# DMXto16Ch.net
KiCad netlist of a schematic drawn in EAGLE
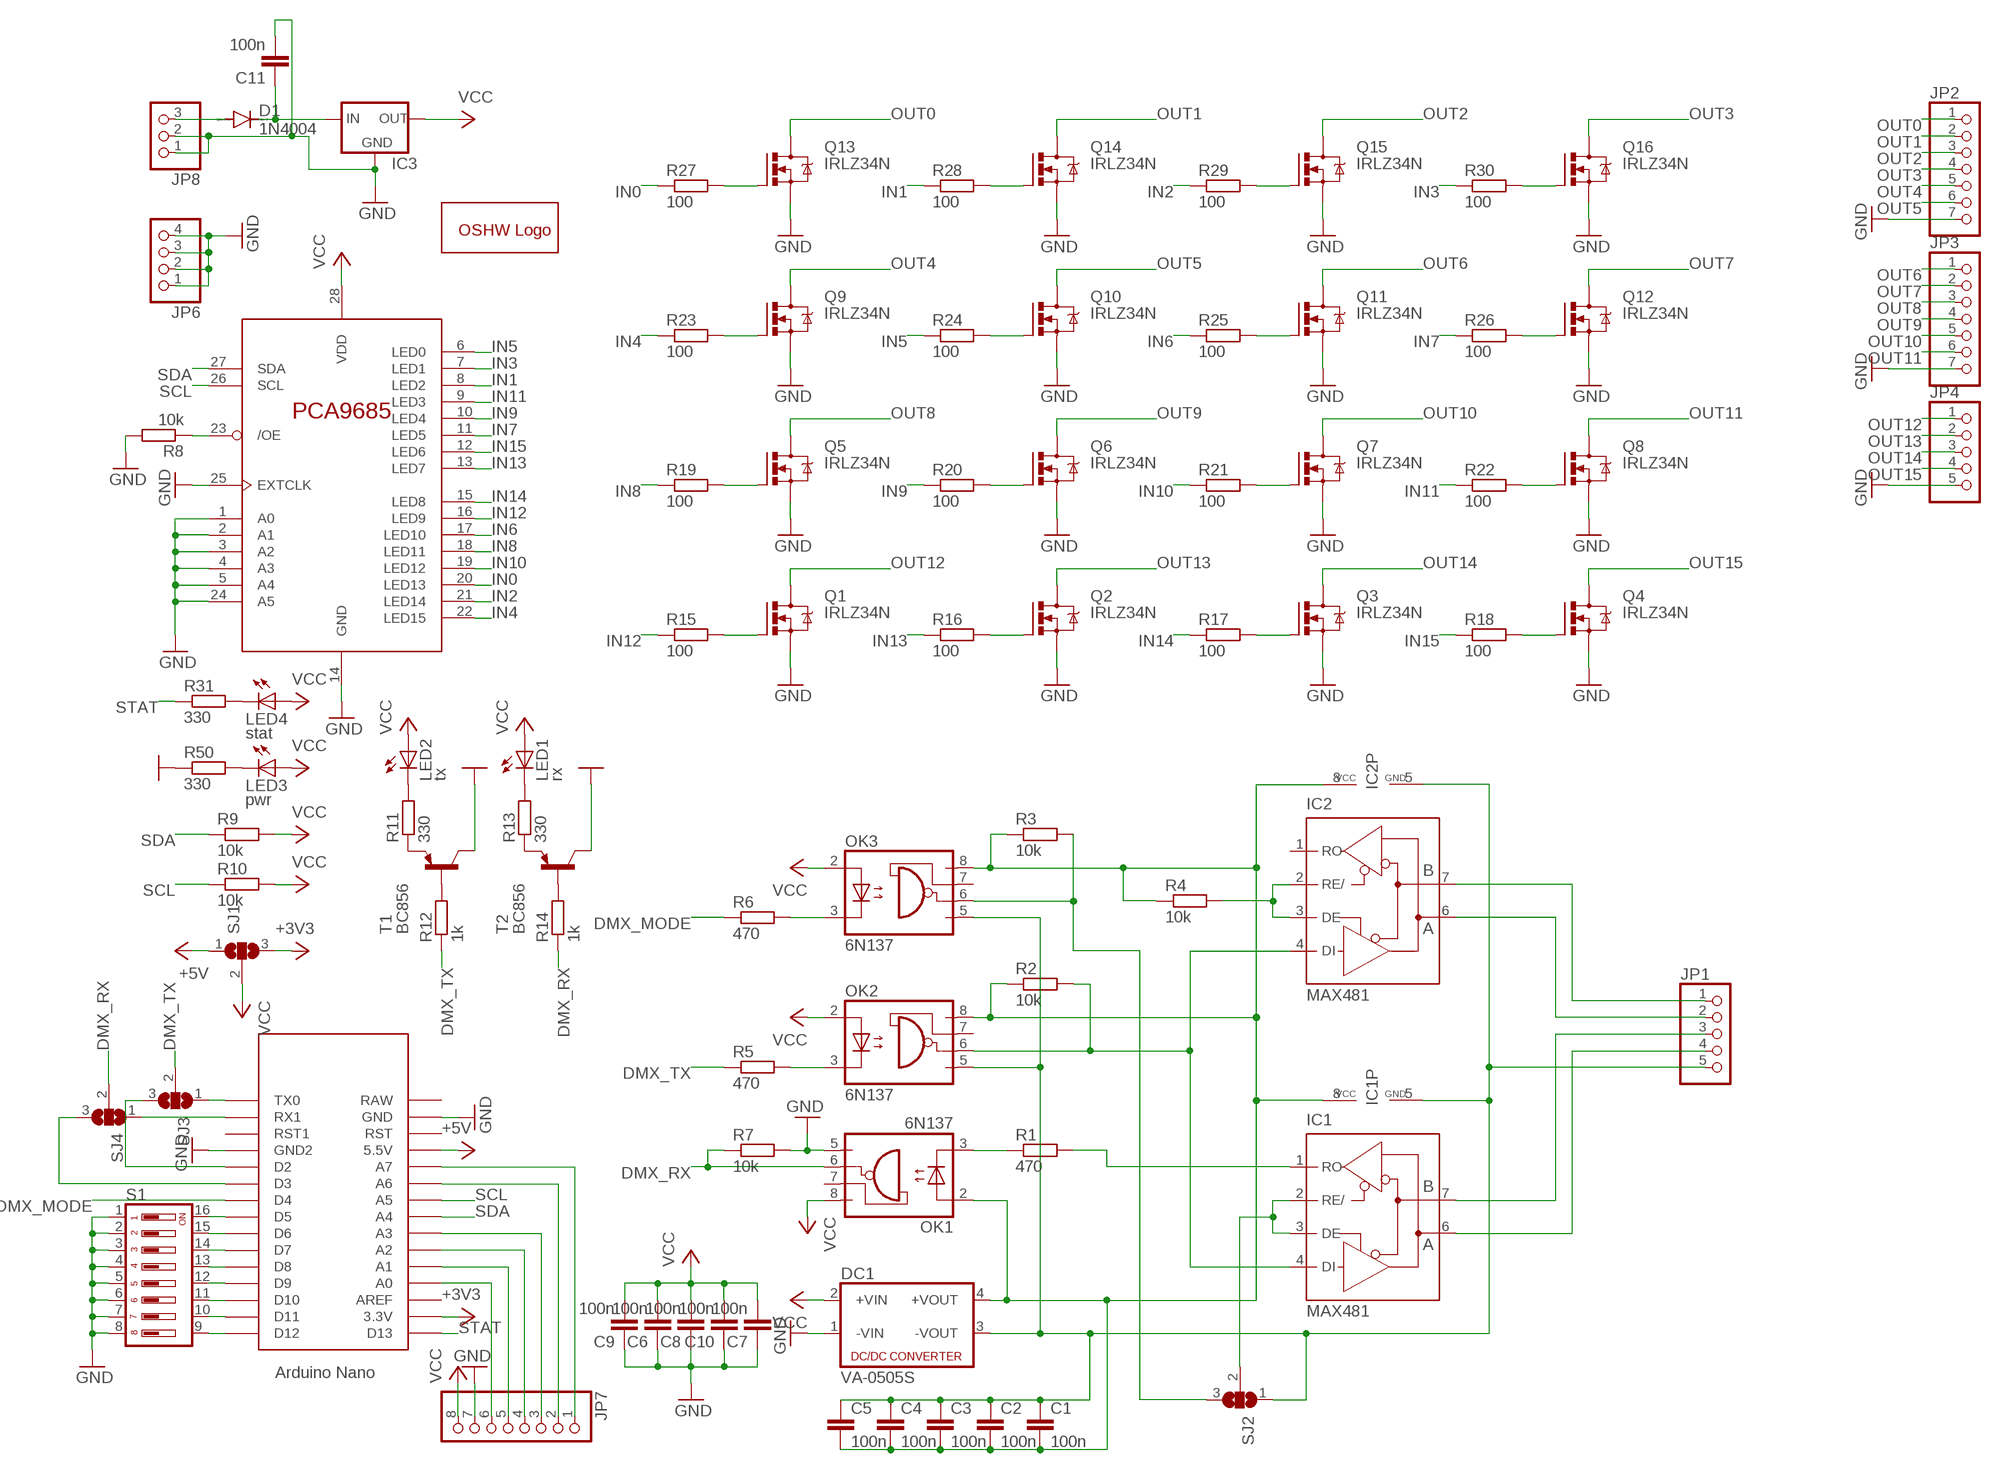
[diagram p0: schematic, sheet 1]

(export (version "E")
  (design (tool "Eeschema 10.0.6"))
  (components
    (comp (ref "C1")
      (value "100n")
      (footprint "eagle-import:C1206")
      (libsource (lib "eagle-import") (part "C-EUC1206"))
    )
    (comp (ref "C2")
      (value "100n")
      (footprint "eagle-import:C1206")
      (libsource (lib "eagle-import") (part "C-EUC1206"))
    )
    (comp (ref "C3")
      (value "100n")
      (footprint "eagle-import:C1206")
      (libsource (lib "eagle-import") (part "C-EUC1206"))
    )
    (comp (ref "C4")
      (value "100n")
      (footprint "eagle-import:C1206")
      (libsource (lib "eagle-import") (part "C-EUC1206"))
    )
    (comp (ref "C5")
      (value "100n")
      (footprint "eagle-import:C1206")
      (libsource (lib "eagle-import") (part "C-EUC1206"))
    )
    (comp (ref "C6")
      (value "100n")
      (footprint "eagle-import:C1206")
      (libsource (lib "eagle-import") (part "C-EUC1206"))
    )
    (comp (ref "C7")
      (value "100n")
      (footprint "eagle-import:C1206")
      (libsource (lib "eagle-import") (part "C-EUC1206"))
    )
    (comp (ref "C8")
      (value "100n")
      (footprint "eagle-import:C1206")
      (libsource (lib "eagle-import") (part "C-EUC1206"))
    )
    (comp (ref "C9")
      (value "100n")
      (footprint "eagle-import:C1206")
      (libsource (lib "eagle-import") (part "C-EUC1206"))
    )
    (comp (ref "C10")
      (value "100n")
      (footprint "eagle-import:C1206")
      (libsource (lib "eagle-import") (part "C-EUC1206"))
    )
    (comp (ref "C11")
      (value "100n")
      (footprint "eagle-import:C1206")
      (libsource (lib "eagle-import") (part "C-EUC1206"))
    )
    (comp (ref "D1")
      (value "1N4004")
      (footprint "eagle-import:DO41-10")
      (libsource (lib "eagle-import") (part "1N4004"))
    )
    (comp (ref "DC1")
      (value "VA-0505S")
      (footprint "eagle-import:4SIL")
      (libsource (lib "eagle-import") (part "VA-?S0505"))
    )
    (comp (ref "GOLD_ORB_SM1")
      (value "OSHWLOGOLOGO5MM")
      (footprint "eagle-import:OSHW_5MM")
      (libsource (lib "eagle-import") (part "OSHWLOGOLOGO5MM"))
    )
    (comp (ref "IC1")
      (value "MAX481")
      (footprint "eagle-import:DIL08")
      (libsource (lib "eagle-import") (part "MAX481CPA"))
    )
    (comp (ref "IC2")
      (value "MAX481")
      (footprint "eagle-import:DIL08")
      (libsource (lib "eagle-import") (part "MAX481CPA"))
    )
    (comp (ref "IC3")
      (value "78XXS")
      (footprint "eagle-import:78XXS")
      (libsource (lib "eagle-import") (part "78XXS"))
    )
    (comp (ref "JP1")
      (value "PINHD-1X5")
      (footprint "eagle-import:1X05")
      (libsource (lib "eagle-import") (part "PINHD-1X5"))
    )
    (comp (ref "JP2")
      (value "PINHD-1X7")
      (footprint "eagle-import:1X07")
      (libsource (lib "eagle-import") (part "PINHD-1X7"))
    )
    (comp (ref "JP3")
      (value "PINHD-1X7")
      (footprint "eagle-import:1X07")
      (libsource (lib "eagle-import") (part "PINHD-1X7"))
    )
    (comp (ref "JP4")
      (value "PINHD-1X5")
      (footprint "eagle-import:1X05")
      (libsource (lib "eagle-import") (part "PINHD-1X5"))
    )
    (comp (ref "JP6")
      (value "PINHD-1X4")
      (footprint "eagle-import:1X04")
      (libsource (lib "eagle-import") (part "PINHD-1X4"))
    )
    (comp (ref "JP7")
      (value "PINHD-1X8")
      (footprint "eagle-import:1X08")
      (libsource (lib "eagle-import") (part "PINHD-1X8"))
    )
    (comp (ref "JP8")
      (value "PINHD-1X3")
      (footprint "eagle-import:1X03")
      (libsource (lib "eagle-import") (part "PINHD-1X3"))
    )
    (comp (ref "LED1")
      (value "rx")
      (footprint "eagle-import:1206")
      (libsource (lib "eagle-import") (part "LEDSMT1206"))
    )
    (comp (ref "LED2")
      (value "tx")
      (footprint "eagle-import:1206")
      (libsource (lib "eagle-import") (part "LEDSMT1206"))
    )
    (comp (ref "LED3")
      (value "pwr")
      (footprint "eagle-import:1206")
      (libsource (lib "eagle-import") (part "LEDSMT1206"))
    )
    (comp (ref "LED4")
      (value "stat")
      (footprint "eagle-import:1206")
      (libsource (lib "eagle-import") (part "LEDSMT1206"))
    )
    (comp (ref "OK1")
      (value "6N137")
      (footprint "eagle-import:DIL08")
      (libsource (lib "eagle-import") (part "6N137"))
    )
    (comp (ref "OK2")
      (value "6N137")
      (footprint "eagle-import:DIL08")
      (libsource (lib "eagle-import") (part "6N137"))
    )
    (comp (ref "OK3")
      (value "6N137")
      (footprint "eagle-import:DIL08")
      (libsource (lib "eagle-import") (part "6N137"))
    )
    (comp (ref "Q1")
      (value "IRLZ34N")
      (footprint "eagle-import:TO220BV")
      (libsource (lib "eagle-import") (part "IRF520"))
    )
    (comp (ref "Q2")
      (value "IRLZ34N")
      (footprint "eagle-import:TO220BV")
      (libsource (lib "eagle-import") (part "IRF520"))
    )
    (comp (ref "Q3")
      (value "IRLZ34N")
      (footprint "eagle-import:TO220BV")
      (libsource (lib "eagle-import") (part "IRF520"))
    )
    (comp (ref "Q4")
      (value "IRLZ34N")
      (footprint "eagle-import:TO220BV")
      (libsource (lib "eagle-import") (part "IRF520"))
    )
    (comp (ref "Q5")
      (value "IRLZ34N")
      (footprint "eagle-import:TO220BV")
      (libsource (lib "eagle-import") (part "IRF520"))
    )
    (comp (ref "Q6")
      (value "IRLZ34N")
      (footprint "eagle-import:TO220BV")
      (libsource (lib "eagle-import") (part "IRF520"))
    )
    (comp (ref "Q7")
      (value "IRLZ34N")
      (footprint "eagle-import:TO220BV")
      (libsource (lib "eagle-import") (part "IRF520"))
    )
    (comp (ref "Q8")
      (value "IRLZ34N")
      (footprint "eagle-import:TO220BV")
      (libsource (lib "eagle-import") (part "IRF520"))
    )
    (comp (ref "Q9")
      (value "IRLZ34N")
      (footprint "eagle-import:TO220BV")
      (libsource (lib "eagle-import") (part "IRF520"))
    )
    (comp (ref "Q10")
      (value "IRLZ34N")
      (footprint "eagle-import:TO220BV")
      (libsource (lib "eagle-import") (part "IRF520"))
    )
    (comp (ref "Q11")
      (value "IRLZ34N")
      (footprint "eagle-import:TO220BV")
      (libsource (lib "eagle-import") (part "IRF520"))
    )
    (comp (ref "Q12")
      (value "IRLZ34N")
      (footprint "eagle-import:TO220BV")
      (libsource (lib "eagle-import") (part "IRF520"))
    )
    (comp (ref "Q13")
      (value "IRLZ34N")
      (footprint "eagle-import:TO220BV")
      (libsource (lib "eagle-import") (part "IRF520"))
    )
    (comp (ref "Q14")
      (value "IRLZ34N")
      (footprint "eagle-import:TO220BV")
      (libsource (lib "eagle-import") (part "IRF520"))
    )
    (comp (ref "Q15")
      (value "IRLZ34N")
      (footprint "eagle-import:TO220BV")
      (libsource (lib "eagle-import") (part "IRF520"))
    )
    (comp (ref "Q16")
      (value "IRLZ34N")
      (footprint "eagle-import:TO220BV")
      (libsource (lib "eagle-import") (part "IRF520"))
    )
    (comp (ref "R1")
      (value "470")
      (footprint "eagle-import:R1206")
      (libsource (lib "eagle-import") (part "R-EU_R1206"))
    )
    (comp (ref "R2")
      (value "10k")
      (footprint "eagle-import:R1206")
      (libsource (lib "eagle-import") (part "R-EU_R1206"))
    )
    (comp (ref "R3")
      (value "10k")
      (footprint "eagle-import:R1206")
      (libsource (lib "eagle-import") (part "R-EU_R1206"))
    )
    (comp (ref "R4")
      (value "10k")
      (footprint "eagle-import:R1206")
      (libsource (lib "eagle-import") (part "R-EU_R1206"))
    )
    (comp (ref "R5")
      (value "470")
      (footprint "eagle-import:R1206")
      (libsource (lib "eagle-import") (part "R-EU_R1206"))
    )
    (comp (ref "R6")
      (value "470")
      (footprint "eagle-import:R1206")
      (libsource (lib "eagle-import") (part "R-EU_R1206"))
    )
    (comp (ref "R7")
      (value "10k")
      (footprint "eagle-import:R1206")
      (libsource (lib "eagle-import") (part "R-EU_R1206"))
    )
    (comp (ref "R8")
      (value "10k")
      (footprint "eagle-import:R1206")
      (libsource (lib "eagle-import") (part "R-EU_R1206"))
    )
    (comp (ref "R9")
      (value "10k")
      (footprint "eagle-import:R1206")
      (libsource (lib "eagle-import") (part "R-EU_R1206"))
    )
    (comp (ref "R10")
      (value "10k")
      (footprint "eagle-import:R1206")
      (libsource (lib "eagle-import") (part "R-EU_R1206"))
    )
    (comp (ref "R11")
      (value "330")
      (footprint "eagle-import:R1206")
      (libsource (lib "eagle-import") (part "R-EU_R1206"))
    )
    (comp (ref "R12")
      (value "1k")
      (footprint "eagle-import:R1206")
      (libsource (lib "eagle-import") (part "R-EU_R1206"))
    )
    (comp (ref "R13")
      (value "330")
      (footprint "eagle-import:R1206")
      (libsource (lib "eagle-import") (part "R-EU_R1206"))
    )
    (comp (ref "R14")
      (value "1k")
      (footprint "eagle-import:R1206")
      (libsource (lib "eagle-import") (part "R-EU_R1206"))
    )
    (comp (ref "R15")
      (value "100")
      (footprint "eagle-import:R1206")
      (libsource (lib "eagle-import") (part "R-EU_R1206"))
    )
    (comp (ref "R16")
      (value "100")
      (footprint "eagle-import:R1206")
      (libsource (lib "eagle-import") (part "R-EU_R1206"))
    )
    (comp (ref "R17")
      (value "100")
      (footprint "eagle-import:R1206")
      (libsource (lib "eagle-import") (part "R-EU_R1206"))
    )
    (comp (ref "R18")
      (value "100")
      (footprint "eagle-import:R1206")
      (libsource (lib "eagle-import") (part "R-EU_R1206"))
    )
    (comp (ref "R19")
      (value "100")
      (footprint "eagle-import:R1206")
      (libsource (lib "eagle-import") (part "R-EU_R1206"))
    )
    (comp (ref "R20")
      (value "100")
      (footprint "eagle-import:R1206")
      (libsource (lib "eagle-import") (part "R-EU_R1206"))
    )
    (comp (ref "R21")
      (value "100")
      (footprint "eagle-import:R1206")
      (libsource (lib "eagle-import") (part "R-EU_R1206"))
    )
    (comp (ref "R22")
      (value "100")
      (footprint "eagle-import:R1206")
      (libsource (lib "eagle-import") (part "R-EU_R1206"))
    )
    (comp (ref "R23")
      (value "100")
      (footprint "eagle-import:R1206")
      (libsource (lib "eagle-import") (part "R-EU_R1206"))
    )
    (comp (ref "R24")
      (value "100")
      (footprint "eagle-import:R1206")
      (libsource (lib "eagle-import") (part "R-EU_R1206"))
    )
    (comp (ref "R25")
      (value "100")
      (footprint "eagle-import:R1206")
      (libsource (lib "eagle-import") (part "R-EU_R1206"))
    )
    (comp (ref "R26")
      (value "100")
      (footprint "eagle-import:R1206")
      (libsource (lib "eagle-import") (part "R-EU_R1206"))
    )
    (comp (ref "R27")
      (value "100")
      (footprint "eagle-import:R1206")
      (libsource (lib "eagle-import") (part "R-EU_R1206"))
    )
    (comp (ref "R28")
      (value "100")
      (footprint "eagle-import:R1206")
      (libsource (lib "eagle-import") (part "R-EU_R1206"))
    )
    (comp (ref "R29")
      (value "100")
      (footprint "eagle-import:R1206")
      (libsource (lib "eagle-import") (part "R-EU_R1206"))
    )
    (comp (ref "R30")
      (value "100")
      (footprint "eagle-import:R1206")
      (libsource (lib "eagle-import") (part "R-EU_R1206"))
    )
    (comp (ref "R31")
      (value "330")
      (footprint "eagle-import:R1206")
      (libsource (lib "eagle-import") (part "R-EU_R1206"))
    )
    (comp (ref "R50")
      (value "330")
      (footprint "eagle-import:R1206")
      (libsource (lib "eagle-import") (part "R-EU_R1206"))
    )
    (comp (ref "S1")
      (value "DIP08YL")
      (footprint "eagle-import:DIP08YL")
      (libsource (lib "eagle-import") (part "DIP08YL"))
    )
    (comp (ref "SJ1")
      (value "SJ2W")
      (footprint "eagle-import:SJ_2")
      (libsource (lib "eagle-import") (part "SJ2W"))
    )
    (comp (ref "SJ2")
      (value "SJ2W")
      (footprint "eagle-import:SJ_2")
      (libsource (lib "eagle-import") (part "SJ2W"))
    )
    (comp (ref "SJ3")
      (value "SJ2W")
      (footprint "eagle-import:SJ_2")
      (libsource (lib "eagle-import") (part "SJ2W"))
    )
    (comp (ref "SJ4")
      (value "SJ2W")
      (footprint "eagle-import:SJ_2")
      (libsource (lib "eagle-import") (part "SJ2W"))
    )
    (comp (ref "T1")
      (value "BC856")
      (footprint "eagle-import:SOT23-BCE")
      (libsource (lib "eagle-import") (part "-PNP-SOT23-BCE"))
    )
    (comp (ref "T2")
      (value "BC856")
      (footprint "eagle-import:SOT23-BCE")
      (libsource (lib "eagle-import") (part "-PNP-SOT23-BCE"))
    )
    (comp (ref "U$1")
      (value "NANO")
      (footprint "eagle-import:NANO")
      (libsource (lib "eagle-import") (part "NANO"))
    )
    (comp (ref "U$2")
      (value "PCA9685PW")
      (footprint "eagle-import:TSSOP28")
      (libsource (lib "eagle-import") (part "PCA9685PW"))
    )
  )
  (nets
    (net (code "1") (name "+3V3") (class "Default")
      (node (ref "SJ1") (pin "3") (pinfunction "3_3") (pintype "passive"))
      (node (ref "U$1") (pin "3.3V") (pinfunction "3.3V_3.3V") (pintype "bidirectional"))
    )
    (net (code "2") (name "+5V") (class "Default")
      (node (ref "SJ1") (pin "1") (pinfunction "1_1") (pintype "passive"))
      (node (ref "U$1") (pin "5V") (pinfunction "5.5V_5V") (pintype "bidirectional"))
    )
    (net (code "3") (name "/DMX_MODE") (class "Default")
      (node (ref "R6") (pin "1") (pinfunction "1_1") (pintype "passive"))
      (node (ref "U$1") (pin "D4") (pinfunction "D4_D4") (pintype "bidirectional"))
    )
    (net (code "4") (name "/DMX_RX") (class "Default")
      (node (ref "OK1") (pin "6") (pinfunction "VO_6") (pintype "passive"))
      (node (ref "R14") (pin "1") (pinfunction "1_1") (pintype "passive"))
      (node (ref "R7") (pin "1") (pinfunction "1_1") (pintype "passive"))
      (node (ref "SJ4") (pin "2") (pinfunction "2_2") (pintype "passive"))
    )
    (net (code "5") (name "/DMX_TX") (class "Default")
      (node (ref "R12") (pin "1") (pinfunction "1_1") (pintype "passive"))
      (node (ref "R5") (pin "1") (pinfunction "1_1") (pintype "passive"))
      (node (ref "SJ3") (pin "2") (pinfunction "2_2") (pintype "passive"))
    )
    (net (code "6") (name "/IN0") (class "Default")
      (node (ref "R27") (pin "1") (pinfunction "1_1") (pintype "passive"))
      (node (ref "U$2") (pin "20") (pinfunction "LED13_20") (pintype "bidirectional"))
    )
    (net (code "7") (name "/IN1") (class "Default")
      (node (ref "R28") (pin "1") (pinfunction "1_1") (pintype "passive"))
      (node (ref "U$2") (pin "8") (pinfunction "LED2_8") (pintype "bidirectional"))
    )
    (net (code "8") (name "/IN2") (class "Default")
      (node (ref "R29") (pin "1") (pinfunction "1_1") (pintype "passive"))
      (node (ref "U$2") (pin "21") (pinfunction "LED14_21") (pintype "bidirectional"))
    )
    (net (code "9") (name "/IN3") (class "Default")
      (node (ref "R30") (pin "1") (pinfunction "1_1") (pintype "passive"))
      (node (ref "U$2") (pin "7") (pinfunction "LED1_7") (pintype "bidirectional"))
    )
    (net (code "10") (name "/IN4") (class "Default")
      (node (ref "R23") (pin "1") (pinfunction "1_1") (pintype "passive"))
      (node (ref "U$2") (pin "22") (pinfunction "LED15_22") (pintype "bidirectional"))
    )
    (net (code "11") (name "/IN5") (class "Default")
      (node (ref "R24") (pin "1") (pinfunction "1_1") (pintype "passive"))
      (node (ref "U$2") (pin "6") (pinfunction "LED0_6") (pintype "bidirectional"))
    )
    (net (code "12") (name "/IN6") (class "Default")
      (node (ref "R25") (pin "1") (pinfunction "1_1") (pintype "passive"))
      (node (ref "U$2") (pin "17") (pinfunction "LED10_17") (pintype "bidirectional"))
    )
    (net (code "13") (name "/IN7") (class "Default")
      (node (ref "R26") (pin "1") (pinfunction "1_1") (pintype "passive"))
      (node (ref "U$2") (pin "11") (pinfunction "LED5_11") (pintype "bidirectional"))
    )
    (net (code "14") (name "/IN8") (class "Default")
      (node (ref "R19") (pin "1") (pinfunction "1_1") (pintype "passive"))
      (node (ref "U$2") (pin "18") (pinfunction "LED11_18") (pintype "bidirectional"))
    )
    (net (code "15") (name "/IN9") (class "Default")
      (node (ref "R20") (pin "1") (pinfunction "1_1") (pintype "passive"))
      (node (ref "U$2") (pin "10") (pinfunction "LED4_10") (pintype "bidirectional"))
    )
    (net (code "16") (name "/IN10") (class "Default")
      (node (ref "R21") (pin "1") (pinfunction "1_1") (pintype "passive"))
      (node (ref "U$2") (pin "19") (pinfunction "LED12_19") (pintype "bidirectional"))
    )
    (net (code "17") (name "/IN11") (class "Default")
      (node (ref "R22") (pin "1") (pinfunction "1_1") (pintype "passive"))
      (node (ref "U$2") (pin "9") (pinfunction "LED3_9") (pintype "bidirectional"))
    )
    (net (code "18") (name "/IN12") (class "Default")
      (node (ref "R15") (pin "1") (pinfunction "1_1") (pintype "passive"))
      (node (ref "U$2") (pin "16") (pinfunction "LED9_16") (pintype "bidirectional"))
    )
    (net (code "19") (name "/IN13") (class "Default")
      (node (ref "R16") (pin "1") (pinfunction "1_1") (pintype "passive"))
      (node (ref "U$2") (pin "13") (pinfunction "LED7_13") (pintype "bidirectional"))
    )
    (net (code "20") (name "/IN14") (class "Default")
      (node (ref "R17") (pin "1") (pinfunction "1_1") (pintype "passive"))
      (node (ref "U$2") (pin "15") (pinfunction "LED8_15") (pintype "bidirectional"))
    )
    (net (code "21") (name "/IN15") (class "Default")
      (node (ref "R18") (pin "1") (pinfunction "1_1") (pintype "passive"))
      (node (ref "U$2") (pin "12") (pinfunction "LED6_12") (pintype "bidirectional"))
    )
    (net (code "22") (name "/OUT0") (class "Default")
      (node (ref "JP2") (pin "1") (pinfunction "1_1") (pintype "passive"))
      (node (ref "Q13") (pin "D") (pinfunction "D_D") (pintype "passive"))
    )
    (net (code "23") (name "/OUT1") (class "Default")
      (node (ref "JP2") (pin "2") (pinfunction "2_2") (pintype "passive"))
      (node (ref "Q14") (pin "D") (pinfunction "D_D") (pintype "passive"))
    )
    (net (code "24") (name "/OUT2") (class "Default")
      (node (ref "JP2") (pin "3") (pinfunction "3_3") (pintype "passive"))
      (node (ref "Q15") (pin "D") (pinfunction "D_D") (pintype "passive"))
    )
    (net (code "25") (name "/OUT3") (class "Default")
      (node (ref "JP2") (pin "4") (pinfunction "4_4") (pintype "passive"))
      (node (ref "Q16") (pin "D") (pinfunction "D_D") (pintype "passive"))
    )
    (net (code "26") (name "/OUT4") (class "Default")
      (node (ref "JP2") (pin "5") (pinfunction "5_5") (pintype "passive"))
      (node (ref "Q9") (pin "D") (pinfunction "D_D") (pintype "passive"))
    )
    (net (code "27") (name "/OUT5") (class "Default")
      (node (ref "JP2") (pin "6") (pinfunction "6_6") (pintype "passive"))
      (node (ref "Q10") (pin "D") (pinfunction "D_D") (pintype "passive"))
    )
    (net (code "28") (name "/OUT6") (class "Default")
      (node (ref "JP3") (pin "1") (pinfunction "1_1") (pintype "passive"))
      (node (ref "Q11") (pin "D") (pinfunction "D_D") (pintype "passive"))
    )
    (net (code "29") (name "/OUT7") (class "Default")
      (node (ref "JP3") (pin "2") (pinfunction "2_2") (pintype "passive"))
      (node (ref "Q12") (pin "D") (pinfunction "D_D") (pintype "passive"))
    )
    (net (code "30") (name "/OUT8") (class "Default")
      (node (ref "JP3") (pin "3") (pinfunction "3_3") (pintype "passive"))
      (node (ref "Q5") (pin "D") (pinfunction "D_D") (pintype "passive"))
    )
    (net (code "31") (name "/OUT9") (class "Default")
      (node (ref "JP3") (pin "4") (pinfunction "4_4") (pintype "passive"))
      (node (ref "Q6") (pin "D") (pinfunction "D_D") (pintype "passive"))
    )
    (net (code "32") (name "/OUT10") (class "Default")
      (node (ref "JP3") (pin "5") (pinfunction "5_5") (pintype "passive"))
      (node (ref "Q7") (pin "D") (pinfunction "D_D") (pintype "passive"))
    )
    (net (code "33") (name "/OUT11") (class "Default")
      (node (ref "JP3") (pin "6") (pinfunction "6_6") (pintype "passive"))
      (node (ref "Q8") (pin "D") (pinfunction "D_D") (pintype "passive"))
    )
    (net (code "34") (name "/OUT12") (class "Default")
      (node (ref "JP4") (pin "1") (pinfunction "1_1") (pintype "passive"))
      (node (ref "Q1") (pin "D") (pinfunction "D_D") (pintype "passive"))
    )
    (net (code "35") (name "/OUT13") (class "Default")
      (node (ref "JP4") (pin "2") (pinfunction "2_2") (pintype "passive"))
      (node (ref "Q2") (pin "D") (pinfunction "D_D") (pintype "passive"))
    )
    (net (code "36") (name "/OUT14") (class "Default")
      (node (ref "JP4") (pin "3") (pinfunction "3_3") (pintype "passive"))
      (node (ref "Q3") (pin "D") (pinfunction "D_D") (pintype "passive"))
    )
    (net (code "37") (name "/OUT15") (class "Default")
      (node (ref "JP4") (pin "4") (pinfunction "4_4") (pintype "passive"))
      (node (ref "Q4") (pin "D") (pinfunction "D_D") (pintype "passive"))
    )
    (net (code "38") (name "/SCL") (class "Default")
      (node (ref "R10") (pin "1") (pinfunction "1_1") (pintype "passive"))
      (node (ref "U$1") (pin "A5") (pinfunction "A5_A5") (pintype "bidirectional"))
      (node (ref "U$2") (pin "26") (pinfunction "SCL_26") (pintype "bidirectional"))
    )
    (net (code "39") (name "/SDA") (class "Default")
      (node (ref "R9") (pin "1") (pinfunction "1_1") (pintype "passive"))
      (node (ref "U$1") (pin "A4") (pinfunction "A4_A4") (pintype "bidirectional"))
      (node (ref "U$2") (pin "27") (pinfunction "SDA_27") (pintype "bidirectional"))
    )
    (net (code "40") (name "/STAT") (class "Default")
      (node (ref "R31") (pin "1") (pinfunction "1_1") (pintype "passive"))
      (node (ref "U$1") (pin "D13") (pinfunction "D13_D13") (pintype "bidirectional"))
    )
    (net (code "41") (name "GND") (class "Default")
      (node (ref "C10") (pin "1") (pinfunction "1_1") (pintype "passive"))
      (node (ref "C11") (pin "2") (pinfunction "2_2") (pintype "passive"))
      (node (ref "C6") (pin "1") (pinfunction "1_1") (pintype "passive"))
      (node (ref "C7") (pin "1") (pinfunction "1_1") (pintype "passive"))
      (node (ref "C8") (pin "1") (pinfunction "1_1") (pintype "passive"))
      (node (ref "C9") (pin "1") (pinfunction "1_1") (pintype "passive"))
      (node (ref "DC1") (pin "1") (pinfunction "-VIN_1") (pintype "passive"))
      (node (ref "IC3") (pin "GND") (pinfunction "GND_GND") (pintype "input"))
      (node (ref "JP2") (pin "7") (pinfunction "7_7") (pintype "passive"))
      (node (ref "JP3") (pin "7") (pinfunction "7_7") (pintype "passive"))
      (node (ref "JP4") (pin "5") (pinfunction "5_5") (pintype "passive"))
      (node (ref "JP6") (pin "1") (pinfunction "1_1") (pintype "passive"))
      (node (ref "JP6") (pin "2") (pinfunction "2_2") (pintype "passive"))
      (node (ref "JP6") (pin "3") (pinfunction "3_3") (pintype "passive"))
      (node (ref "JP6") (pin "4") (pinfunction "4_4") (pintype "passive"))
      (node (ref "JP7") (pin "7") (pinfunction "7_7") (pintype "passive"))
      (node (ref "JP8") (pin "1") (pinfunction "1_1") (pintype "passive"))
      (node (ref "JP8") (pin "2") (pinfunction "2_2") (pintype "passive"))
      (node (ref "OK1") (pin "5") (pinfunction "GND_5") (pintype "passive"))
      (node (ref "Q1") (pin "S") (pinfunction "S_S") (pintype "passive"))
      (node (ref "Q10") (pin "S") (pinfunction "S_S") (pintype "passive"))
      (node (ref "Q11") (pin "S") (pinfunction "S_S") (pintype "passive"))
      (node (ref "Q12") (pin "S") (pinfunction "S_S") (pintype "passive"))
      (node (ref "Q13") (pin "S") (pinfunction "S_S") (pintype "passive"))
      (node (ref "Q14") (pin "S") (pinfunction "S_S") (pintype "passive"))
      (node (ref "Q15") (pin "S") (pinfunction "S_S") (pintype "passive"))
      (node (ref "Q16") (pin "S") (pinfunction "S_S") (pintype "passive"))
      (node (ref "Q2") (pin "S") (pinfunction "S_S") (pintype "passive"))
      (node (ref "Q3") (pin "S") (pinfunction "S_S") (pintype "passive"))
      (node (ref "Q4") (pin "S") (pinfunction "S_S") (pintype "passive"))
      (node (ref "Q5") (pin "S") (pinfunction "S_S") (pintype "passive"))
      (node (ref "Q6") (pin "S") (pinfunction "S_S") (pintype "passive"))
      (node (ref "Q7") (pin "S") (pinfunction "S_S") (pintype "passive"))
      (node (ref "Q8") (pin "S") (pinfunction "S_S") (pintype "passive"))
      (node (ref "Q9") (pin "S") (pinfunction "S_S") (pintype "passive"))
      (node (ref "R50") (pin "1") (pinfunction "1_1") (pintype "passive"))
      (node (ref "R7") (pin "2") (pinfunction "2_2") (pintype "passive"))
      (node (ref "R8") (pin "2") (pinfunction "2_2") (pintype "passive"))
      (node (ref "S1") (pin "1") (pinfunction "1_1") (pintype "passive"))
      (node (ref "S1") (pin "2") (pinfunction "2_2") (pintype "passive"))
      (node (ref "S1") (pin "3") (pinfunction "3_3") (pintype "passive"))
      (node (ref "S1") (pin "4") (pinfunction "4_4") (pintype "passive"))
      (node (ref "S1") (pin "5") (pinfunction "5_5") (pintype "passive"))
      (node (ref "S1") (pin "6") (pinfunction "6_6") (pintype "passive"))
      (node (ref "S1") (pin "7") (pinfunction "7_7") (pintype "passive"))
      (node (ref "S1") (pin "8") (pinfunction "8_8") (pintype "passive"))
      (node (ref "T1") (pin "C") (pinfunction "C_C") (pintype "passive"))
      (node (ref "T2") (pin "C") (pinfunction "C_C") (pintype "passive"))
      (node (ref "U$1") (pin "GND") (pinfunction "GND_GND") (pintype "bidirectional"))
      (node (ref "U$1") (pin "GND1") (pinfunction "GND2_GND1") (pintype "bidirectional"))
      (node (ref "U$2") (pin "1") (pinfunction "A0_1") (pintype "bidirectional"))
      (node (ref "U$2") (pin "14") (pinfunction "GND_14") (pintype "power_in"))
      (node (ref "U$2") (pin "2") (pinfunction "A1_2") (pintype "bidirectional"))
      (node (ref "U$2") (pin "24") (pinfunction "A5_24") (pintype "bidirectional"))
      (node (ref "U$2") (pin "25") (pinfunction "EXTCLK_25") (pintype "input"))
      (node (ref "U$2") (pin "3") (pinfunction "A2_3") (pintype "bidirectional"))
      (node (ref "U$2") (pin "4") (pinfunction "A3_4") (pintype "bidirectional"))
      (node (ref "U$2") (pin "5") (pinfunction "A4_5") (pintype "bidirectional"))
    )
    (net (code "42") (name "Net-(C11-Pad1)") (class "Default")
      (node (ref "C11") (pin "1") (pinfunction "1_1") (pintype "passive"))
      (node (ref "D1") (pin "C") (pinfunction "C_C") (pintype "passive"))
      (node (ref "IC3") (pin "IN") (pinfunction "IN_IN") (pintype "input"))
    )
    (net (code "43") (name "Net-(D1-PadA)") (class "Default")
      (node (ref "D1") (pin "A") (pinfunction "A_A") (pintype "passive"))
      (node (ref "JP8") (pin "3") (pinfunction "3_3") (pintype "passive"))
    )
    (net (code "44") (name "Net-(DC1-+VOUT)") (class "Default")
      (node (ref "C1") (pin "2") (pinfunction "2_2") (pintype "passive"))
      (node (ref "C2") (pin "2") (pinfunction "2_2") (pintype "passive"))
      (node (ref "C3") (pin "2") (pinfunction "2_2") (pintype "passive"))
      (node (ref "C4") (pin "2") (pinfunction "2_2") (pintype "passive"))
      (node (ref "C5") (pin "2") (pinfunction "2_2") (pintype "passive"))
      (node (ref "DC1") (pin "4") (pinfunction "+VOUT_4") (pintype "passive"))
      (node (ref "IC1") (pin "8") (pinfunction "VCC_8") (pintype "power_in"))
      (node (ref "IC2") (pin "8") (pinfunction "VCC_8") (pintype "power_in"))
      (node (ref "OK1") (pin "2") (pinfunction "A_2") (pintype "passive"))
      (node (ref "OK2") (pin "8") (pinfunction "VCC_8") (pintype "passive"))
      (node (ref "OK3") (pin "8") (pinfunction "VCC_8") (pintype "passive"))
      (node (ref "R2") (pin "1") (pinfunction "1_1") (pintype "passive"))
      (node (ref "R3") (pin "1") (pinfunction "1_1") (pintype "passive"))
      (node (ref "R4") (pin "1") (pinfunction "1_1") (pintype "passive"))
    )
    (net (code "45") (name "Net-(DC1--VOUT)") (class "Default")
      (node (ref "C1") (pin "1") (pinfunction "1_1") (pintype "passive"))
      (node (ref "C2") (pin "1") (pinfunction "1_1") (pintype "passive"))
      (node (ref "C3") (pin "1") (pinfunction "1_1") (pintype "passive"))
      (node (ref "C4") (pin "1") (pinfunction "1_1") (pintype "passive"))
      (node (ref "C5") (pin "1") (pinfunction "1_1") (pintype "passive"))
      (node (ref "DC1") (pin "3") (pinfunction "-VOUT_3") (pintype "passive"))
      (node (ref "IC1") (pin "5") (pinfunction "GND_5") (pintype "power_in"))
      (node (ref "IC2") (pin "5") (pinfunction "GND_5") (pintype "power_in"))
      (node (ref "JP1") (pin "5") (pinfunction "5_5") (pintype "passive"))
      (node (ref "OK2") (pin "5") (pinfunction "GND_5") (pintype "passive"))
      (node (ref "OK3") (pin "5") (pinfunction "GND_5") (pintype "passive"))
      (node (ref "SJ2") (pin "1") (pinfunction "1_1") (pintype "passive"))
    )
    (net (code "46") (name "Net-(IC1A-A)") (class "Default")
      (node (ref "IC1") (pin "6") (pinfunction "A_6") (pintype "passive"))
      (node (ref "JP1") (pin "4") (pinfunction "4_4") (pintype "passive"))
    )
    (net (code "47") (name "Net-(IC1A-B)") (class "Default")
      (node (ref "IC1") (pin "7") (pinfunction "B_7") (pintype "passive"))
      (node (ref "JP1") (pin "3") (pinfunction "3_3") (pintype "passive"))
    )
    (net (code "48") (name "Net-(IC1A-DE)") (class "Default")
      (node (ref "IC1") (pin "2") (pinfunction "RE/_2") (pintype "input"))
      (node (ref "IC1") (pin "3") (pinfunction "DE_3") (pintype "input"))
      (node (ref "SJ2") (pin "2") (pinfunction "2_2") (pintype "passive"))
    )
    (net (code "49") (name "Net-(IC1A-DI)") (class "Default")
      (node (ref "IC1") (pin "4") (pinfunction "DI_4") (pintype "input"))
      (node (ref "IC2") (pin "4") (pinfunction "DI_4") (pintype "input"))
      (node (ref "OK2") (pin "6") (pinfunction "VO_6") (pintype "passive"))
      (node (ref "R2") (pin "2") (pinfunction "2_2") (pintype "passive"))
    )
    (net (code "50") (name "Net-(IC1A-RO)") (class "Default")
      (node (ref "IC1") (pin "1") (pinfunction "RO_1") (pintype "output"))
      (node (ref "R1") (pin "2") (pinfunction "2_2") (pintype "passive"))
    )
    (net (code "51") (name "Net-(IC2A-A)") (class "Default")
      (node (ref "IC2") (pin "6") (pinfunction "A_6") (pintype "passive"))
      (node (ref "JP1") (pin "2") (pinfunction "2_2") (pintype "passive"))
    )
    (net (code "52") (name "Net-(IC2A-B)") (class "Default")
      (node (ref "IC2") (pin "7") (pinfunction "B_7") (pintype "passive"))
      (node (ref "JP1") (pin "1") (pinfunction "1_1") (pintype "passive"))
    )
    (net (code "53") (name "Net-(IC2A-DE)") (class "Default")
      (node (ref "IC2") (pin "2") (pinfunction "RE/_2") (pintype "input"))
      (node (ref "IC2") (pin "3") (pinfunction "DE_3") (pintype "input"))
      (node (ref "R4") (pin "2") (pinfunction "2_2") (pintype "passive"))
    )
    (net (code "54") (name "Net-(JP7-Pad1)") (class "Default")
      (node (ref "JP7") (pin "1") (pinfunction "1_1") (pintype "passive"))
      (node (ref "U$1") (pin "A7") (pinfunction "A7_A7") (pintype "bidirectional"))
    )
    (net (code "55") (name "Net-(JP7-Pad2)") (class "Default")
      (node (ref "JP7") (pin "2") (pinfunction "2_2") (pintype "passive"))
      (node (ref "U$1") (pin "A6") (pinfunction "A6_A6") (pintype "bidirectional"))
    )
    (net (code "56") (name "Net-(JP7-Pad3)") (class "Default")
      (node (ref "JP7") (pin "3") (pinfunction "3_3") (pintype "passive"))
      (node (ref "U$1") (pin "A3") (pinfunction "A3_A3") (pintype "bidirectional"))
    )
    (net (code "57") (name "Net-(JP7-Pad4)") (class "Default")
      (node (ref "JP7") (pin "4") (pinfunction "4_4") (pintype "passive"))
      (node (ref "U$1") (pin "A2") (pinfunction "A2_A2") (pintype "bidirectional"))
    )
    (net (code "58") (name "Net-(JP7-Pad5)") (class "Default")
      (node (ref "JP7") (pin "5") (pinfunction "5_5") (pintype "passive"))
      (node (ref "U$1") (pin "A1") (pinfunction "A1_A1") (pintype "bidirectional"))
    )
    (net (code "59") (name "Net-(JP7-Pad6)") (class "Default")
      (node (ref "JP7") (pin "6") (pinfunction "6_6") (pintype "passive"))
      (node (ref "U$1") (pin "A0") (pinfunction "A0_A0") (pintype "bidirectional"))
    )
    (net (code "60") (name "Net-(LED1-PadC)") (class "Default")
      (node (ref "LED1") (pin "C") (pinfunction "C_C") (pintype "passive"))
      (node (ref "R13") (pin "2") (pinfunction "2_2") (pintype "passive"))
    )
    (net (code "61") (name "Net-(LED2-PadC)") (class "Default")
      (node (ref "LED2") (pin "C") (pinfunction "C_C") (pintype "passive"))
      (node (ref "R11") (pin "2") (pinfunction "2_2") (pintype "passive"))
    )
    (net (code "62") (name "Net-(LED3-PadC)") (class "Default")
      (node (ref "LED3") (pin "C") (pinfunction "C_C") (pintype "passive"))
      (node (ref "R50") (pin "2") (pinfunction "2_2") (pintype "passive"))
    )
    (net (code "63") (name "Net-(LED4-PadC)") (class "Default")
      (node (ref "LED4") (pin "C") (pinfunction "C_C") (pintype "passive"))
      (node (ref "R31") (pin "2") (pinfunction "2_2") (pintype "passive"))
    )
    (net (code "64") (name "Net-(OK1-C)") (class "Default")
      (node (ref "OK1") (pin "3") (pinfunction "C_3") (pintype "passive"))
      (node (ref "R1") (pin "1") (pinfunction "1_1") (pintype "passive"))
    )
    (net (code "65") (name "Net-(OK2-C)") (class "Default")
      (node (ref "OK2") (pin "3") (pinfunction "C_3") (pintype "passive"))
      (node (ref "R5") (pin "2") (pinfunction "2_2") (pintype "passive"))
    )
    (net (code "66") (name "Net-(OK3-C)") (class "Default")
      (node (ref "OK3") (pin "3") (pinfunction "C_3") (pintype "passive"))
      (node (ref "R6") (pin "2") (pinfunction "2_2") (pintype "passive"))
    )
    (net (code "67") (name "Net-(OK3-VO)") (class "Default")
      (node (ref "OK3") (pin "6") (pinfunction "VO_6") (pintype "passive"))
      (node (ref "R3") (pin "2") (pinfunction "2_2") (pintype "passive"))
      (node (ref "SJ2") (pin "3") (pinfunction "3_3") (pintype "passive"))
    )
    (net (code "68") (name "Net-(Q1-PadG)") (class "Default")
      (node (ref "Q1") (pin "G") (pinfunction "G_G") (pintype "passive"))
      (node (ref "R15") (pin "2") (pinfunction "2_2") (pintype "passive"))
    )
    (net (code "69") (name "Net-(Q2-PadG)") (class "Default")
      (node (ref "Q2") (pin "G") (pinfunction "G_G") (pintype "passive"))
      (node (ref "R16") (pin "2") (pinfunction "2_2") (pintype "passive"))
    )
    (net (code "70") (name "Net-(Q3-PadG)") (class "Default")
      (node (ref "Q3") (pin "G") (pinfunction "G_G") (pintype "passive"))
      (node (ref "R17") (pin "2") (pinfunction "2_2") (pintype "passive"))
    )
    (net (code "71") (name "Net-(Q4-PadG)") (class "Default")
      (node (ref "Q4") (pin "G") (pinfunction "G_G") (pintype "passive"))
      (node (ref "R18") (pin "2") (pinfunction "2_2") (pintype "passive"))
    )
    (net (code "72") (name "Net-(Q5-PadG)") (class "Default")
      (node (ref "Q5") (pin "G") (pinfunction "G_G") (pintype "passive"))
      (node (ref "R19") (pin "2") (pinfunction "2_2") (pintype "passive"))
    )
    (net (code "73") (name "Net-(Q6-PadG)") (class "Default")
      (node (ref "Q6") (pin "G") (pinfunction "G_G") (pintype "passive"))
      (node (ref "R20") (pin "2") (pinfunction "2_2") (pintype "passive"))
    )
    (net (code "74") (name "Net-(Q7-PadG)") (class "Default")
      (node (ref "Q7") (pin "G") (pinfunction "G_G") (pintype "passive"))
      (node (ref "R21") (pin "2") (pinfunction "2_2") (pintype "passive"))
    )
    (net (code "75") (name "Net-(Q8-PadG)") (class "Default")
      (node (ref "Q8") (pin "G") (pinfunction "G_G") (pintype "passive"))
      (node (ref "R22") (pin "2") (pinfunction "2_2") (pintype "passive"))
    )
    (net (code "76") (name "Net-(Q9-PadG)") (class "Default")
      (node (ref "Q9") (pin "G") (pinfunction "G_G") (pintype "passive"))
      (node (ref "R23") (pin "2") (pinfunction "2_2") (pintype "passive"))
    )
    (net (code "77") (name "Net-(Q10-PadG)") (class "Default")
      (node (ref "Q10") (pin "G") (pinfunction "G_G") (pintype "passive"))
      (node (ref "R24") (pin "2") (pinfunction "2_2") (pintype "passive"))
    )
    (net (code "78") (name "Net-(Q11-PadG)") (class "Default")
      (node (ref "Q11") (pin "G") (pinfunction "G_G") (pintype "passive"))
      (node (ref "R25") (pin "2") (pinfunction "2_2") (pintype "passive"))
    )
    (net (code "79") (name "Net-(Q12-PadG)") (class "Default")
      (node (ref "Q12") (pin "G") (pinfunction "G_G") (pintype "passive"))
      (node (ref "R26") (pin "2") (pinfunction "2_2") (pintype "passive"))
    )
    (net (code "80") (name "Net-(Q13-PadG)") (class "Default")
      (node (ref "Q13") (pin "G") (pinfunction "G_G") (pintype "passive"))
      (node (ref "R27") (pin "2") (pinfunction "2_2") (pintype "passive"))
    )
    (net (code "81") (name "Net-(Q14-PadG)") (class "Default")
      (node (ref "Q14") (pin "G") (pinfunction "G_G") (pintype "passive"))
      (node (ref "R28") (pin "2") (pinfunction "2_2") (pintype "passive"))
    )
    (net (code "82") (name "Net-(Q15-PadG)") (class "Default")
      (node (ref "Q15") (pin "G") (pinfunction "G_G") (pintype "passive"))
      (node (ref "R29") (pin "2") (pinfunction "2_2") (pintype "passive"))
    )
    (net (code "83") (name "Net-(Q16-PadG)") (class "Default")
      (node (ref "Q16") (pin "G") (pinfunction "G_G") (pintype "passive"))
      (node (ref "R30") (pin "2") (pinfunction "2_2") (pintype "passive"))
    )
    (net (code "84") (name "Net-(R11-Pad1)") (class "Default")
      (node (ref "R11") (pin "1") (pinfunction "1_1") (pintype "passive"))
      (node (ref "T1") (pin "E") (pinfunction "E_E") (pintype "passive"))
    )
    (net (code "85") (name "Net-(R12-Pad2)") (class "Default")
      (node (ref "R12") (pin "2") (pinfunction "2_2") (pintype "passive"))
      (node (ref "T1") (pin "B") (pinfunction "B_B") (pintype "passive"))
    )
    (net (code "86") (name "Net-(R13-Pad1)") (class "Default")
      (node (ref "R13") (pin "1") (pinfunction "1_1") (pintype "passive"))
      (node (ref "T2") (pin "E") (pinfunction "E_E") (pintype "passive"))
    )
    (net (code "87") (name "Net-(R14-Pad2)") (class "Default")
      (node (ref "R14") (pin "2") (pinfunction "2_2") (pintype "passive"))
      (node (ref "T2") (pin "B") (pinfunction "B_B") (pintype "passive"))
    )
    (net (code "88") (name "Net-(S1-Pad9)") (class "Default")
      (node (ref "S1") (pin "9") (pinfunction "9_9") (pintype "passive"))
      (node (ref "U$1") (pin "D12") (pinfunction "D12_D12") (pintype "bidirectional"))
    )
    (net (code "89") (name "Net-(S1-Pad10)") (class "Default")
      (node (ref "S1") (pin "10") (pinfunction "10_10") (pintype "passive"))
      (node (ref "U$1") (pin "D11") (pinfunction "D11_D11") (pintype "bidirectional"))
    )
    (net (code "90") (name "Net-(S1-Pad11)") (class "Default")
      (node (ref "S1") (pin "11") (pinfunction "11_11") (pintype "passive"))
      (node (ref "U$1") (pin "D10") (pinfunction "D10_D10") (pintype "bidirectional"))
    )
    (net (code "91") (name "Net-(S1-Pad12)") (class "Default")
      (node (ref "S1") (pin "12") (pinfunction "12_12") (pintype "passive"))
      (node (ref "U$1") (pin "D9") (pinfunction "D9_D9") (pintype "bidirectional"))
    )
    (net (code "92") (name "Net-(S1-Pad13)") (class "Default")
      (node (ref "S1") (pin "13") (pinfunction "13_13") (pintype "passive"))
      (node (ref "U$1") (pin "D8") (pinfunction "D8_D8") (pintype "bidirectional"))
    )
    (net (code "93") (name "Net-(S1-Pad14)") (class "Default")
      (node (ref "S1") (pin "14") (pinfunction "14_14") (pintype "passive"))
      (node (ref "U$1") (pin "D7") (pinfunction "D7_D7") (pintype "bidirectional"))
    )
    (net (code "94") (name "Net-(S1-Pad15)") (class "Default")
      (node (ref "S1") (pin "15") (pinfunction "15_15") (pintype "passive"))
      (node (ref "U$1") (pin "D6") (pinfunction "D6_D6") (pintype "bidirectional"))
    )
    (net (code "95") (name "Net-(S1-Pad16)") (class "Default")
      (node (ref "S1") (pin "16") (pinfunction "16_16") (pintype "passive"))
      (node (ref "U$1") (pin "D5") (pinfunction "D5_D5") (pintype "bidirectional"))
    )
    (net (code "96") (name "Net-(SJ3-Pad1)") (class "Default")
      (node (ref "SJ3") (pin "1") (pinfunction "1_1") (pintype "passive"))
      (node (ref "U$1") (pin "TX0") (pinfunction "TX0_TX0") (pintype "bidirectional"))
    )
    (net (code "97") (name "Net-(SJ3-Pad3)") (class "Default")
      (node (ref "SJ3") (pin "3") (pinfunction "3_3") (pintype "passive"))
      (node (ref "U$1") (pin "D2") (pinfunction "D2_D2") (pintype "bidirectional"))
    )
    (net (code "98") (name "Net-(SJ4-Pad1)") (class "Default")
      (node (ref "SJ4") (pin "1") (pinfunction "1_1") (pintype "passive"))
      (node (ref "U$1") (pin "RX1") (pinfunction "RX1_RX1") (pintype "bidirectional"))
    )
    (net (code "99") (name "Net-(SJ4-Pad3)") (class "Default")
      (node (ref "SJ4") (pin "3") (pinfunction "3_3") (pintype "passive"))
      (node (ref "U$1") (pin "D3") (pinfunction "D3_D3") (pintype "bidirectional"))
    )
    (net (code "100") (name "Net-(U$2-{slash}OE)") (class "Default")
      (node (ref "R8") (pin "1") (pinfunction "1_1") (pintype "passive"))
      (node (ref "U$2") (pin "23") (pinfunction "/OE_23") (pintype "bidirectional"))
    )
    (net (code "101") (name "VCC") (class "Default")
      (node (ref "C10") (pin "2") (pinfunction "2_2") (pintype "passive"))
      (node (ref "C6") (pin "2") (pinfunction "2_2") (pintype "passive"))
      (node (ref "C7") (pin "2") (pinfunction "2_2") (pintype "passive"))
      (node (ref "C8") (pin "2") (pinfunction "2_2") (pintype "passive"))
      (node (ref "C9") (pin "2") (pinfunction "2_2") (pintype "passive"))
      (node (ref "DC1") (pin "2") (pinfunction "+VIN_2") (pintype "passive"))
      (node (ref "IC3") (pin "OUT") (pinfunction "OUT_OUT") (pintype "passive"))
      (node (ref "JP7") (pin "8") (pinfunction "8_8") (pintype "passive"))
      (node (ref "LED1") (pin "A") (pinfunction "A_A") (pintype "passive"))
      (node (ref "LED2") (pin "A") (pinfunction "A_A") (pintype "passive"))
      (node (ref "LED3") (pin "A") (pinfunction "A_A") (pintype "passive"))
      (node (ref "LED4") (pin "A") (pinfunction "A_A") (pintype "passive"))
      (node (ref "OK1") (pin "8") (pinfunction "VCC_8") (pintype "passive"))
      (node (ref "OK2") (pin "2") (pinfunction "A_2") (pintype "passive"))
      (node (ref "OK3") (pin "2") (pinfunction "A_2") (pintype "passive"))
      (node (ref "R10") (pin "2") (pinfunction "2_2") (pintype "passive"))
      (node (ref "R9") (pin "2") (pinfunction "2_2") (pintype "passive"))
      (node (ref "SJ1") (pin "2") (pinfunction "2_2") (pintype "passive"))
      (node (ref "U$2") (pin "28") (pinfunction "VDD_28") (pintype "power_in"))
    )
    (net (code "102") (name "unconnected-(IC2A-RO-Pad1)") (class "Default")
      (node (ref "IC2") (pin "1") (pinfunction "RO_1") (pintype "output"))
    )
    (net (code "103") (name "unconnected-(OK1-VE-Pad7)") (class "Default")
      (node (ref "OK1") (pin "7") (pinfunction "VE_7") (pintype "passive"))
    )
    (net (code "104") (name "unconnected-(OK2-VE-Pad7)") (class "Default")
      (node (ref "OK2") (pin "7") (pinfunction "VE_7") (pintype "passive"))
    )
    (net (code "105") (name "unconnected-(OK3-VE-Pad7)") (class "Default")
      (node (ref "OK3") (pin "7") (pinfunction "VE_7") (pintype "passive"))
    )
    (net (code "106") (name "unconnected-(U$1-PadAREF)") (class "Default")
      (node (ref "U$1") (pin "AREF") (pinfunction "AREF_AREF") (pintype "bidirectional"))
    )
    (net (code "107") (name "unconnected-(U$1-PadICSP1)") (class "Default")
      (node (ref "U$1") (pin "ICSP1") (pinfunction "ICSP1_ICSP1") (pintype "bidirectional"))
    )
    (net (code "108") (name "unconnected-(U$1-PadICSP2)") (class "Default")
      (node (ref "U$1") (pin "ICSP2") (pinfunction "ICSP2_ICSP2") (pintype "bidirectional"))
    )
    (net (code "109") (name "unconnected-(U$1-PadICSP3)") (class "Default")
      (node (ref "U$1") (pin "ICSP3") (pinfunction "ICSP3_ICSP3") (pintype "bidirectional"))
    )
    (net (code "110") (name "unconnected-(U$1-PadICSP4)") (class "Default")
      (node (ref "U$1") (pin "ICSP4") (pinfunction "ICSP4_ICSP4") (pintype "bidirectional"))
    )
    (net (code "111") (name "unconnected-(U$1-PadICSP5)") (class "Default")
      (node (ref "U$1") (pin "ICSP5") (pinfunction "ICSP5_ICSP5") (pintype "bidirectional"))
    )
    (net (code "112") (name "unconnected-(U$1-PadICSP6)") (class "Default")
      (node (ref "U$1") (pin "ICSP6") (pinfunction "ICSP6_ICSP6") (pintype "bidirectional"))
    )
    (net (code "113") (name "unconnected-(U$1-PadRAW)") (class "Default")
      (node (ref "U$1") (pin "RAW") (pinfunction "RAW_RAW") (pintype "bidirectional"))
    )
    (net (code "114") (name "unconnected-(U$1-PadRST)") (class "Default")
      (node (ref "U$1") (pin "RST") (pinfunction "RST_RST") (pintype "bidirectional"))
    )
    (net (code "115") (name "unconnected-(U$1-PadRST1)") (class "Default")
      (node (ref "U$1") (pin "RST1") (pinfunction "RST1_RST1") (pintype "bidirectional"))
    )
  )
)
